# STM32F407.net
KiCad netlist of a schematic drawn in Altium Designer
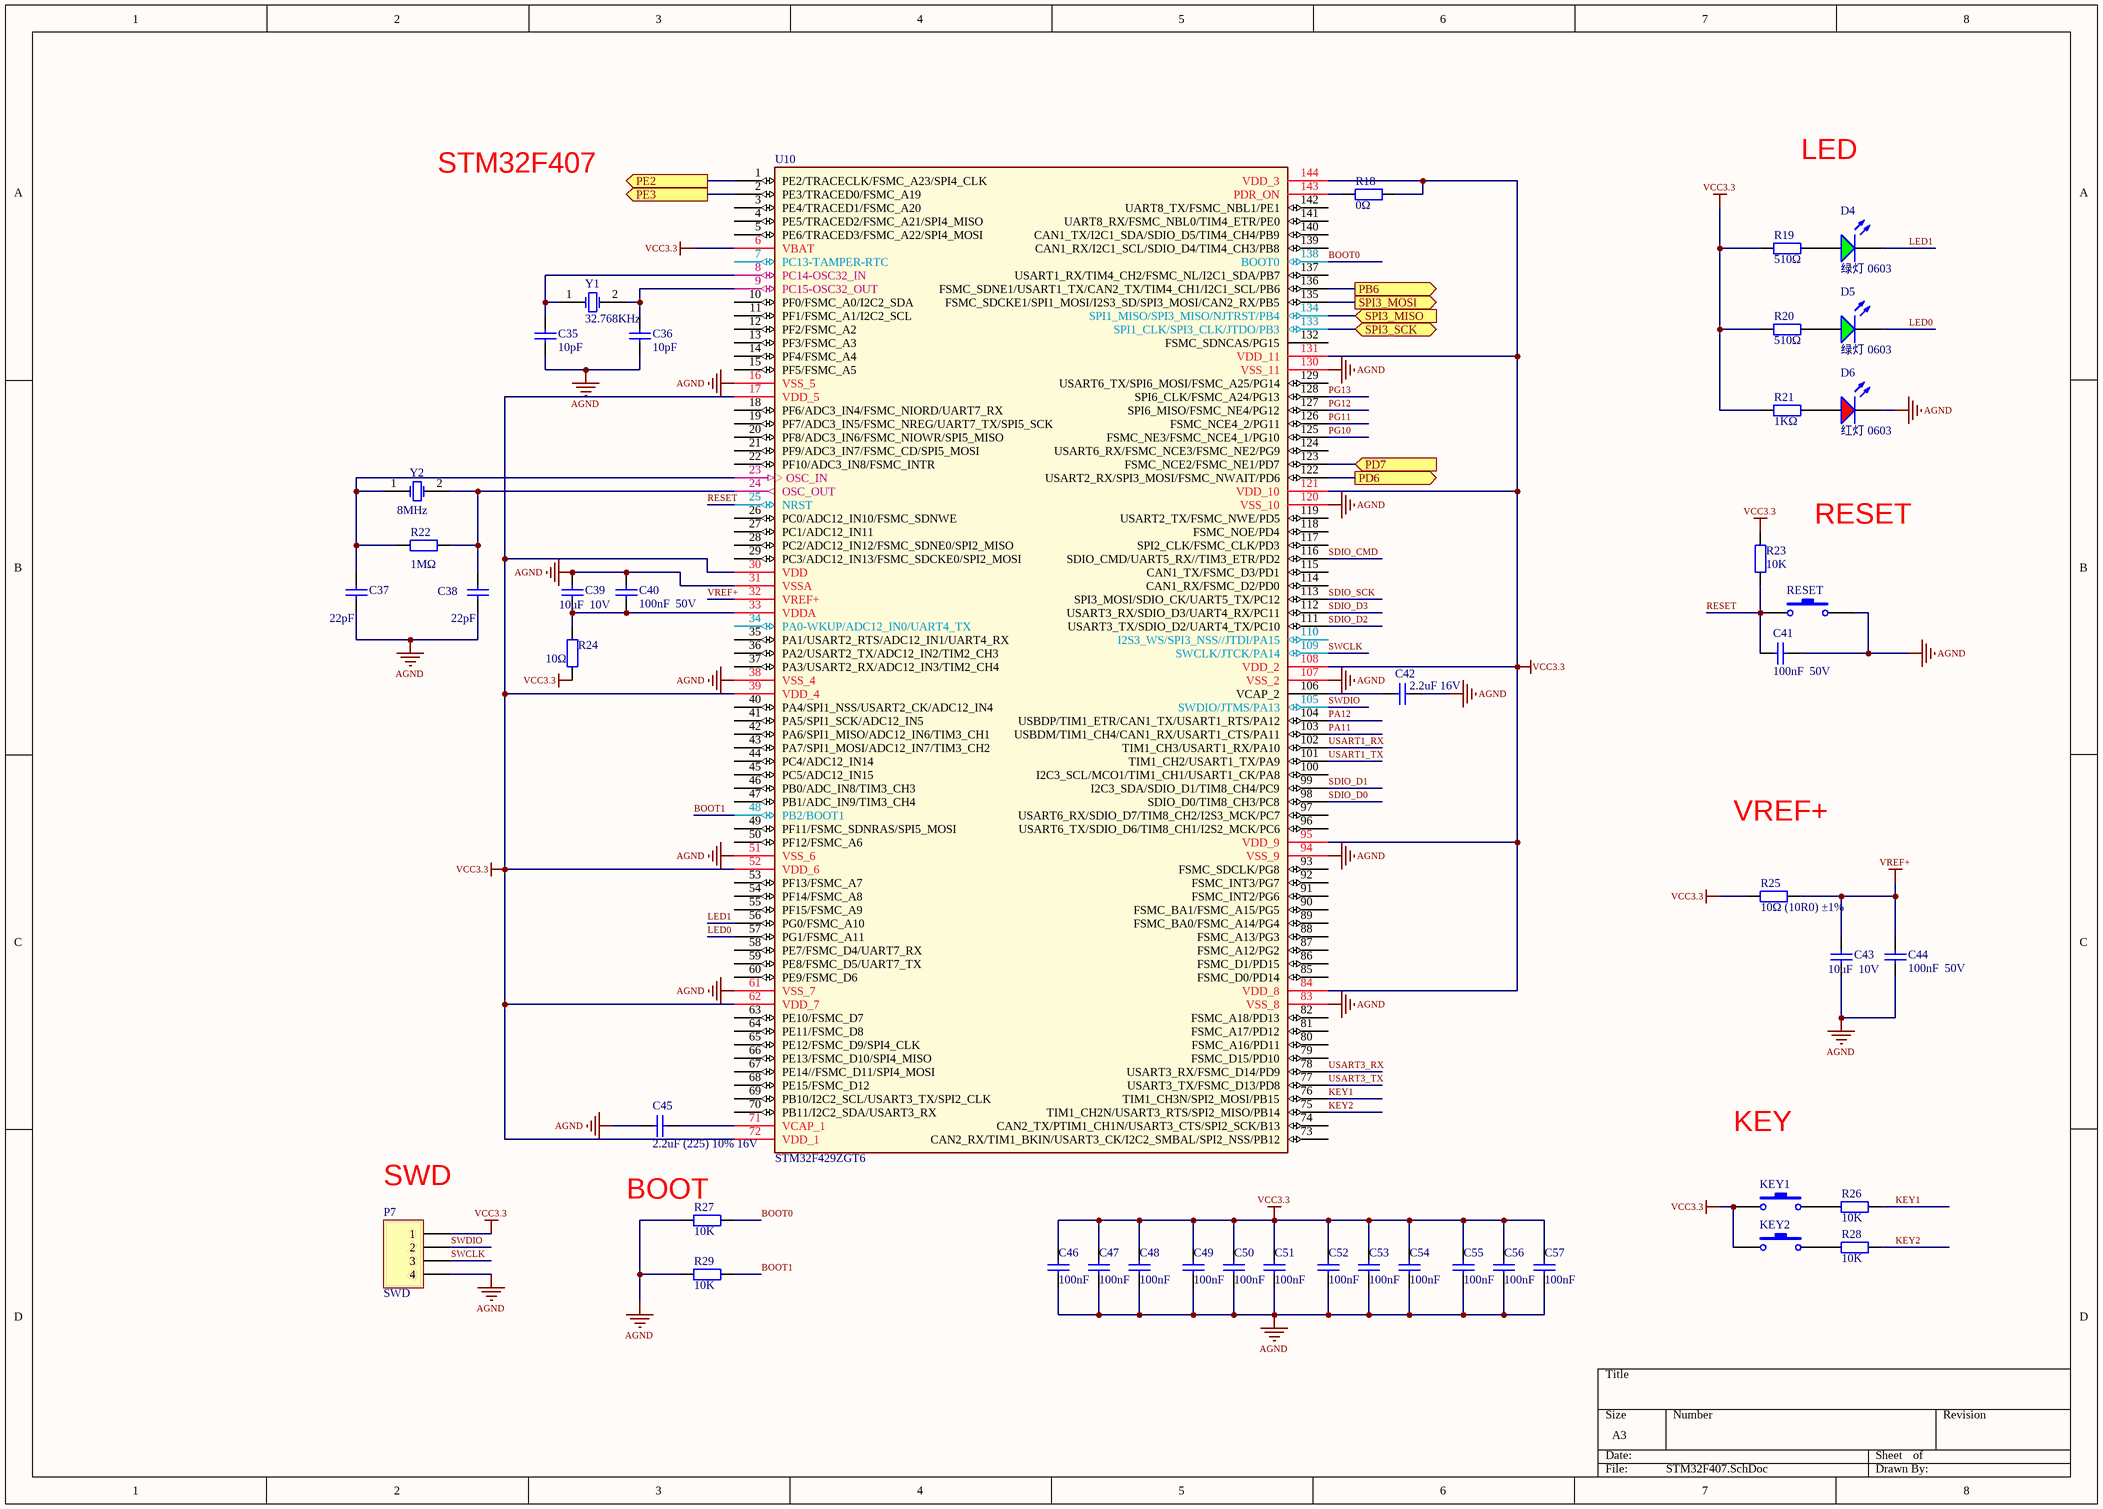
[diagram p0: STM32F407.SchDoc]

(export (version "E")
  (design (tool "Eeschema 10.0.6"))
  (components
    (comp (ref "C35")
      (value "10pF")
      (footprint "0402_C")
      (description "贴片电容")
      (libsource (lib "Miscellaneous Devices LC") (part "0603 10pF (100) 5% 50V"))
    )
    (comp (ref "C36")
      (value "10pF")
      (footprint "0402_C")
      (description "贴片电容")
      (libsource (lib "Miscellaneous Devices LC") (part "0603 10pF (100) 5% 50V"))
    )
    (comp (ref "C37")
      (value "22pF")
      (footprint "0402_C")
      (description "贴片电容")
      (libsource (lib "Miscellaneous Devices LC") (part "0603 22pF (220) 5% 50V"))
    )
    (comp (ref "C38")
      (value "22pF")
      (footprint "0402_C")
      (description "贴片电容")
      (libsource (lib "Miscellaneous Devices LC") (part "0603 22pF (220) 5% 50V"))
    )
    (comp (ref "C39")
      (value "10uF  10V")
      (footprint "0402_C")
      (description "贴片电容")
      (libsource (lib "Miscellaneous Devices LC") (part "0603 10uF (106) 10% 10V"))
    )
    (comp (ref "C40")
      (value "100nF  50V")
      (footprint "0402_C")
      (description "贴片电容")
      (libsource (lib "Miscellaneous Devices LC") (part "0603 100nF (104) 10% 50V"))
    )
    (comp (ref "C41")
      (value "100nF  50V")
      (footprint "0402_C")
      (description "贴片电容")
      (libsource (lib "Miscellaneous Devices LC") (part "0603 100nF (104) 10% 50V"))
    )
    (comp (ref "C42")
      (value "2.2uF 16V")
      (footprint "0603_C")
      (description "贴片电容")
      (libsource (lib "Miscellaneous Devices LC") (part "0603 2.2uF (225) 10% 16V"))
    )
    (comp (ref "C43")
      (value "10uF  10V")
      (footprint "0402_C")
      (description "贴片电容")
      (libsource (lib "Miscellaneous Devices LC") (part "0603 10uF (106) 10% 10V"))
    )
    (comp (ref "C44")
      (value "100nF  50V")
      (footprint "0402_C")
      (description "贴片电容")
      (libsource (lib "Miscellaneous Devices LC") (part "0603 100nF (104) 10% 50V"))
    )
    (comp (ref "C45")
      (value "2.2uF (225) 10% 16V")
      (footprint "0603_C")
      (description "贴片电容")
      (libsource (lib "Miscellaneous Devices LC") (part "0603 2.2uF (225) 10% 16V"))
    )
    (comp (ref "C46")
      (value "100nF")
      (footprint "0402_C")
      (description "贴片电容")
      (libsource (lib "Miscellaneous Devices LC") (part "0402 100nF (104) 10% 16V"))
    )
    (comp (ref "C47")
      (value "100nF")
      (footprint "0402_C")
      (description "贴片电容")
      (libsource (lib "Miscellaneous Devices LC") (part "0402 100nF (104) 10% 16V"))
    )
    (comp (ref "C48")
      (value "100nF")
      (footprint "0402_C")
      (description "贴片电容")
      (libsource (lib "Miscellaneous Devices LC") (part "0402 100nF (104) 10% 16V"))
    )
    (comp (ref "C49")
      (value "100nF")
      (footprint "0402_C")
      (description "贴片电容")
      (libsource (lib "Miscellaneous Devices LC") (part "0402 100nF (104) 10% 16V"))
    )
    (comp (ref "C50")
      (value "100nF")
      (footprint "0402_C")
      (description "贴片电容")
      (libsource (lib "Miscellaneous Devices LC") (part "0402 100nF (104) 10% 16V"))
    )
    (comp (ref "C51")
      (value "100nF")
      (footprint "0402_C")
      (description "贴片电容")
      (libsource (lib "Miscellaneous Devices LC") (part "0402 100nF (104) 10% 16V"))
    )
    (comp (ref "C52")
      (value "100nF")
      (footprint "0402_C")
      (description "贴片电容")
      (libsource (lib "Miscellaneous Devices LC") (part "0402 100nF (104) 10% 16V"))
    )
    (comp (ref "C53")
      (value "100nF")
      (footprint "0402_C")
      (description "贴片电容")
      (libsource (lib "Miscellaneous Devices LC") (part "0402 100nF (104) 10% 16V"))
    )
    (comp (ref "C54")
      (value "100nF")
      (footprint "0402_C")
      (description "贴片电容")
      (libsource (lib "Miscellaneous Devices LC") (part "0402 100nF (104) 10% 16V"))
    )
    (comp (ref "C55")
      (value "100nF")
      (footprint "0402_C")
      (description "贴片电容")
      (libsource (lib "Miscellaneous Devices LC") (part "0402 100nF (104) 10% 16V"))
    )
    (comp (ref "C56")
      (value "100nF")
      (footprint "0402_C")
      (description "贴片电容")
      (libsource (lib "Miscellaneous Devices LC") (part "0402 100nF (104) 10% 16V"))
    )
    (comp (ref "C57")
      (value "100nF")
      (footprint "0402_C")
      (description "贴片电容")
      (libsource (lib "Miscellaneous Devices LC") (part "0402 100nF (104) 10% 16V"))
    )
    (comp (ref "D4")
      (value "绿灯 0603")
      (footprint "0603_LED_S1")
      (description "发光二极管")
      (libsource (lib "Miscellaneous Devices LC") (part "0603 绿灯"))
    )
    (comp (ref "D5")
      (value "绿灯 0603")
      (footprint "0603_LED_S1")
      (description "发光二极管")
      (libsource (lib "Miscellaneous Devices LC") (part "0603 绿灯"))
    )
    (comp (ref "D6")
      (value "红灯 0603")
      (footprint "0603_LED_S1")
      (description "发光二极管")
      (libsource (lib "Miscellaneous Devices LC") (part "0603 红灯"))
    )
    (comp (ref "KEY1")
      (value "SW-PB")
      (footprint "KEY_3.6*2.5")
      (description "Switch")
      (fields (field (name "PUBLISHER") "Altium Limited"))
      (libsource (lib "Miscellaneous Devices") (part "SW-PB"))
    )
    (comp (ref "KEY2")
      (value "SW-PB")
      (footprint "KEY_3.6*2.5")
      (description "Switch")
      (fields (field (name "PUBLISHER") "Altium Limited"))
      (libsource (lib "Miscellaneous Devices") (part "SW-PB"))
    )
    (comp (ref "P7")
      (value "SWD")
      (footprint "HDR1X4")
      (description "Header, 4-Pin")
      (fields (field (name "PUBLISHER") "Altium Limited"))
      (libsource (lib "Miscellaneous Connectors") (part "Header 4"))
    )
    (comp (ref "R18")
      (value "0Ω")
      (footprint "0402_R")
      (description "贴片电阻")
      (libsource (lib "Miscellaneous Devices LC") (part "0603 0Ω (0R0) 1%"))
    )
    (comp (ref "R19")
      (value "510Ω")
      (footprint "0402_R")
      (description "贴片电阻")
      (libsource (lib "Miscellaneous Devices LC") (part "0603 510Ω (5100) 1%"))
    )
    (comp (ref "R20")
      (value "510Ω")
      (footprint "0402_R")
      (description "贴片电阻")
      (libsource (lib "Miscellaneous Devices LC") (part "0603 510Ω (5100) 1%"))
    )
    (comp (ref "R21")
      (value "1KΩ")
      (footprint "0402_R")
      (description "贴片电阻")
      (libsource (lib "Miscellaneous Devices LC") (part "0603 1KΩ (1001) 1%"))
    )
    (comp (ref "R22")
      (value "1MΩ")
      (footprint "0402_R")
      (description "贴片电阻")
      (libsource (lib "Miscellaneous Devices LC") (part "0603 1.2MΩ (1204) 1%"))
    )
    (comp (ref "R23")
      (value "10K")
      (footprint "0402_R")
      (description "贴片电阻")
      (libsource (lib "") (part "0603 10Ω (10R0) 1%_2"))
    )
    (comp (ref "R24")
      (value "10Ω")
      (footprint "0402_R")
      (description "贴片电阻")
      (libsource (lib "") (part "0603 10Ω (10R0) 1%_1"))
    )
    (comp (ref "R25")
      (value "10Ω (10R0) ±1%")
      (footprint "0402_R")
      (description "贴片电阻")
      (libsource (lib "") (part "0603 10Ω (10R0) 1%_3"))
    )
    (comp (ref "R26")
      (value "10K")
      (footprint "0402_R")
      (description "贴片电阻")
      (libsource (lib "Miscellaneous Devices LC") (part "0603 10Ω (10R0) 1%"))
    )
    (comp (ref "R27")
      (value "10K")
      (footprint "0402_R")
      (description "贴片电阻")
      (libsource (lib "Miscellaneous Devices LC") (part "0603 10Ω (10R0) 1%"))
    )
    (comp (ref "R28")
      (value "10K")
      (footprint "0402_R")
      (description "贴片电阻")
      (libsource (lib "Miscellaneous Devices LC") (part "0603 10Ω (10R0) 1%"))
    )
    (comp (ref "R29")
      (value "10K")
      (footprint "0402_R")
      (description "贴片电阻")
      (libsource (lib "Miscellaneous Devices LC") (part "0603 10Ω (10R0) 1%"))
    )
    (comp (ref "RESET")
      (value "SW-PB")
      (footprint "KEY_3.6*2.5")
      (description "Switch")
      (fields (field (name "PUBLISHER") "Altium Limited"))
      (libsource (lib "Miscellaneous Devices") (part "SW-PB"))
    )
    (comp (ref "U10")
      (value "STM32F429ZGT6")
      (footprint "LQFP-144_20x20x05P")
      (description "ARM")
      (libsource (lib "Miscellaneous Devices LC") (part "STM32F429ZGT6"))
    )
    (comp (ref "Y1")
      (value "32.768KHz")
      (footprint "SMD-3215_2P FC - 135")
      (description "贴片晶振")
      (libsource (lib "Miscellaneous Devices LC") (part "SMD-3215_2P 32.768KHz 20ppm 12.5pF"))
    )
    (comp (ref "Y2")
      (value "8MHz")
      (footprint "SMD-5032_2P")
      (description "贴片晶振")
      (libsource (lib "Miscellaneous Devices LC") (part "SMD-5032_2P 8MHz 20ppm 20pF"))
    )
  )
  (nets
    (net (code "1") (name "/BOOT0") (class "Default")
      (node (ref "R27") (pin "2") (pinfunction "2_2") (pintype "passive"))
      (node (ref "U10") (pin "138") (pinfunction "BOOT0_138") (pintype "bidirectional"))
    )
    (net (code "2") (name "/BOOT1") (class "Default")
      (node (ref "R29") (pin "2") (pinfunction "2_2") (pintype "passive"))
      (node (ref "U10") (pin "48") (pinfunction "PB2/BOOT1_48") (pintype "bidirectional"))
    )
    (net (code "3") (name "/KEY1") (class "Default")
      (node (ref "R26") (pin "2") (pinfunction "2_2") (pintype "passive"))
      (node (ref "U10") (pin "76") (pinfunction "TIM1_CH3N/SPI2_MOSI/PB15_76") (pintype "bidirectional"))
    )
    (net (code "4") (name "/KEY2") (class "Default")
      (node (ref "R28") (pin "2") (pinfunction "2_2") (pintype "passive"))
      (node (ref "U10") (pin "75") (pinfunction "TIM1_CH2N/USART3_RTS/SPI2_MISO/PB14_75") (pintype "bidirectional"))
    )
    (net (code "5") (name "/LED0") (class "Default")
      (node (ref "D5") (pin "K") (pinfunction "K_K") (pintype "passive"))
      (node (ref "U10") (pin "57") (pinfunction "PG1/FSMC_A11_57") (pintype "bidirectional"))
    )
    (net (code "6") (name "/LED1") (class "Default")
      (node (ref "D4") (pin "K") (pinfunction "K_K") (pintype "passive"))
      (node (ref "U10") (pin "56") (pinfunction "PG0/FSMC_A10_56") (pintype "bidirectional"))
    )
    (net (code "7") (name "/PA11") (class "Default")
      (node (ref "U10") (pin "103") (pinfunction "USBDM/TIM1_CH4/CAN1_RX/USART1_CTS/PA11_103") (pintype "bidirectional"))
    )
    (net (code "8") (name "/PA12") (class "Default")
      (node (ref "U10") (pin "104") (pinfunction "USBDP/TIM1_ETR/CAN1_TX/USART1_RTS/PA12_104") (pintype "bidirectional"))
    )
    (net (code "9") (name "/PB6") (class "Default")
      (node (ref "U10") (pin "136") (pinfunction "FSMC_SDNE1/USART1_TX/CAN2_TX/TIM4_CH1/I2C1_SCL/PB6_136") (pintype "bidirectional"))
    )
    (net (code "10") (name "/PD6") (class "Default")
      (node (ref "U10") (pin "122") (pinfunction "USART2_RX/SPI3_MOSI/FSMC_NWAIT/PD6_122") (pintype "bidirectional"))
    )
    (net (code "11") (name "/PD7") (class "Default")
      (node (ref "U10") (pin "123") (pinfunction "FSMC_NCE2/FSMC_NE1/PD7_123") (pintype "bidirectional"))
    )
    (net (code "12") (name "/PE2") (class "Default")
      (node (ref "U10") (pin "1") (pinfunction "PE2/TRACECLK/FSMC_A23/SPI4_CLK_1") (pintype "bidirectional"))
    )
    (net (code "13") (name "/PE3") (class "Default")
      (node (ref "U10") (pin "2") (pinfunction "PE3/TRACED0/FSMC_A19_2") (pintype "bidirectional"))
    )
    (net (code "14") (name "/PG10") (class "Default")
      (node (ref "U10") (pin "125") (pinfunction "FSMC_NE3/FSMC_NCE4_1/PG10_125") (pintype "bidirectional"))
    )
    (net (code "15") (name "/PG11") (class "Default")
      (node (ref "U10") (pin "126") (pinfunction "FSMC_NCE4_2/PG11_126") (pintype "bidirectional"))
    )
    (net (code "16") (name "/PG12") (class "Default")
      (node (ref "U10") (pin "127") (pinfunction "SPI6_MISO/FSMC_NE4/PG12_127") (pintype "bidirectional"))
    )
    (net (code "17") (name "/PG13") (class "Default")
      (node (ref "U10") (pin "128") (pinfunction "SPI6_CLK/FSMC_A24/PG13_128") (pintype "bidirectional"))
    )
    (net (code "18") (name "/RESET") (class "Default")
      (node (ref "C41") (pin "2") (pinfunction "2_2") (pintype "passive"))
      (node (ref "R23") (pin "2") (pinfunction "2_2") (pintype "passive"))
      (node (ref "RESET") (pin "1") (pinfunction "1_1") (pintype "passive"))
      (node (ref "U10") (pin "25") (pinfunction "NRST_25") (pintype "bidirectional"))
    )
    (net (code "19") (name "/SDIO_CMD") (class "Default")
      (node (ref "U10") (pin "116") (pinfunction "SDIO_CMD/UART5_RX//TIM3_ETR/PD2_116") (pintype "bidirectional"))
    )
    (net (code "20") (name "/SDIO_D0") (class "Default")
      (node (ref "U10") (pin "98") (pinfunction "SDIO_D0/TIM8_CH3/PC8_98") (pintype "bidirectional"))
    )
    (net (code "21") (name "/SDIO_D1") (class "Default")
      (node (ref "U10") (pin "99") (pinfunction "I2C3_SDA/SDIO_D1/TIM8_CH4/PC9_99") (pintype "bidirectional"))
    )
    (net (code "22") (name "/SDIO_D2") (class "Default")
      (node (ref "U10") (pin "111") (pinfunction "USART3_TX/SDIO_D2/UART4_TX/PC10_111") (pintype "bidirectional"))
    )
    (net (code "23") (name "/SDIO_D3") (class "Default")
      (node (ref "U10") (pin "112") (pinfunction "USART3_RX/SDIO_D3/UART4_RX/PC11_112") (pintype "bidirectional"))
    )
    (net (code "24") (name "/SDIO_SCK") (class "Default")
      (node (ref "U10") (pin "113") (pinfunction "SPI3_MOSI/SDIO_CK/UART5_TX/PC12_113") (pintype "bidirectional"))
    )
    (net (code "25") (name "/SPI3_MISO") (class "Default")
      (node (ref "U10") (pin "134") (pinfunction "SPI1_MISO/SPI3_MISO/NJTRST/PB4_134") (pintype "bidirectional"))
    )
    (net (code "26") (name "/SPI3_MOSI") (class "Default")
      (node (ref "U10") (pin "135") (pinfunction "FSMC_SDCKE1/SPI1_MOSI/I2S3_SD/SPI3_MOSI/CAN2_RX/PB5_135") (pintype "bidirectional"))
    )
    (net (code "27") (name "/SPI3_SCK") (class "Default")
      (node (ref "U10") (pin "133") (pinfunction "SPI1_CLK/SPI3_CLK/JTDO/PB3_133") (pintype "bidirectional"))
    )
    (net (code "28") (name "/SWCLK") (class "Default")
      (node (ref "P7") (pin "3") (pinfunction "3_3") (pintype "passive"))
      (node (ref "U10") (pin "109") (pinfunction "SWCLK/JTCK/PA14_109") (pintype "bidirectional"))
    )
    (net (code "29") (name "/SWDIO") (class "Default")
      (node (ref "P7") (pin "2") (pinfunction "2_2") (pintype "passive"))
      (node (ref "U10") (pin "105") (pinfunction "SWDIO/JTMS/PA13_105") (pintype "bidirectional"))
    )
    (net (code "30") (name "/USART1_RX") (class "Default")
      (node (ref "U10") (pin "102") (pinfunction "TIM1_CH3/USART1_RX/PA10_102") (pintype "bidirectional"))
    )
    (net (code "31") (name "/USART1_TX") (class "Default")
      (node (ref "U10") (pin "101") (pinfunction "TIM1_CH2/USART1_TX/PA9_101") (pintype "bidirectional"))
    )
    (net (code "32") (name "/USART3_RX") (class "Default")
      (node (ref "U10") (pin "78") (pinfunction "USART3_RX/FSMC_D14/PD9_78") (pintype "bidirectional"))
    )
    (net (code "33") (name "/USART3_TX") (class "Default")
      (node (ref "U10") (pin "77") (pinfunction "USART3_TX/FSMC_D13/PD8_77") (pintype "bidirectional"))
    )
    (net (code "34") (name "AGND") (class "Default")
      (node (ref "C35") (pin "1") (pinfunction "1_1") (pintype "passive"))
      (node (ref "C36") (pin "1") (pinfunction "1_1") (pintype "passive"))
      (node (ref "C37") (pin "1") (pinfunction "1_1") (pintype "passive"))
      (node (ref "C38") (pin "1") (pinfunction "1_1") (pintype "passive"))
      (node (ref "C39") (pin "2") (pinfunction "2_2") (pintype "passive"))
      (node (ref "C40") (pin "2") (pinfunction "2_2") (pintype "passive"))
      (node (ref "C41") (pin "1") (pinfunction "1_1") (pintype "passive"))
      (node (ref "C42") (pin "1") (pinfunction "1_1") (pintype "passive"))
      (node (ref "C43") (pin "1") (pinfunction "1_1") (pintype "passive"))
      (node (ref "C44") (pin "1") (pinfunction "1_1") (pintype "passive"))
      (node (ref "C45") (pin "1") (pinfunction "1_1") (pintype "passive"))
      (node (ref "C46") (pin "1") (pinfunction "1_1") (pintype "passive"))
      (node (ref "C47") (pin "1") (pinfunction "1_1") (pintype "passive"))
      (node (ref "C48") (pin "1") (pinfunction "1_1") (pintype "passive"))
      (node (ref "C49") (pin "1") (pinfunction "1_1") (pintype "passive"))
      (node (ref "C50") (pin "1") (pinfunction "1_1") (pintype "passive"))
      (node (ref "C51") (pin "1") (pinfunction "1_1") (pintype "passive"))
      (node (ref "C52") (pin "1") (pinfunction "1_1") (pintype "passive"))
      (node (ref "C53") (pin "1") (pinfunction "1_1") (pintype "passive"))
      (node (ref "C54") (pin "1") (pinfunction "1_1") (pintype "passive"))
      (node (ref "C55") (pin "1") (pinfunction "1_1") (pintype "passive"))
      (node (ref "C56") (pin "1") (pinfunction "1_1") (pintype "passive"))
      (node (ref "C57") (pin "1") (pinfunction "1_1") (pintype "passive"))
      (node (ref "D6") (pin "K") (pinfunction "K_K") (pintype "passive"))
      (node (ref "P7") (pin "4") (pinfunction "4_4") (pintype "passive"))
      (node (ref "R27") (pin "1") (pinfunction "1_1") (pintype "passive"))
      (node (ref "R29") (pin "1") (pinfunction "1_1") (pintype "passive"))
      (node (ref "RESET") (pin "2") (pinfunction "2_2") (pintype "passive"))
      (node (ref "U10") (pin "107") (pinfunction "VSS_2_107") (pintype "power_in"))
      (node (ref "U10") (pin "120") (pinfunction "VSS_10_120") (pintype "power_in"))
      (node (ref "U10") (pin "130") (pinfunction "VSS_11_130") (pintype "power_in"))
      (node (ref "U10") (pin "16") (pinfunction "VSS_5_16") (pintype "power_in"))
      (node (ref "U10") (pin "31") (pinfunction "VSSA_31") (pintype "power_in"))
      (node (ref "U10") (pin "38") (pinfunction "VSS_4_38") (pintype "power_in"))
      (node (ref "U10") (pin "51") (pinfunction "VSS_6_51") (pintype "power_in"))
      (node (ref "U10") (pin "61") (pinfunction "VSS_7_61") (pintype "power_in"))
      (node (ref "U10") (pin "83") (pinfunction "VSS_8_83") (pintype "power_in"))
      (node (ref "U10") (pin "94") (pinfunction "VSS_9_94") (pintype "power_in"))
    )
    (net (code "35") (name "Net-(D4-PadA)") (class "Default")
      (node (ref "D4") (pin "A") (pinfunction "A_A") (pintype "passive"))
      (node (ref "R19") (pin "2") (pinfunction "2_2") (pintype "passive"))
    )
    (net (code "36") (name "Net-(D5-PadA)") (class "Default")
      (node (ref "D5") (pin "A") (pinfunction "A_A") (pintype "passive"))
      (node (ref "R20") (pin "2") (pinfunction "2_2") (pintype "passive"))
    )
    (net (code "37") (name "Net-(D6-PadA)") (class "Default")
      (node (ref "D6") (pin "A") (pinfunction "A_A") (pintype "passive"))
      (node (ref "R21") (pin "2") (pinfunction "2_2") (pintype "passive"))
    )
    (net (code "38") (name "Net-(KEY1-Pad2)") (class "Default")
      (node (ref "KEY1") (pin "2") (pinfunction "2_2") (pintype "passive"))
      (node (ref "R26") (pin "1") (pinfunction "1_1") (pintype "passive"))
    )
    (net (code "39") (name "Net-(KEY2-Pad2)") (class "Default")
      (node (ref "KEY2") (pin "2") (pinfunction "2_2") (pintype "passive"))
      (node (ref "R28") (pin "1") (pinfunction "1_1") (pintype "passive"))
    )
    (net (code "40") (name "Net-(U10-OSC_IN)") (class "Default")
      (node (ref "C37") (pin "2") (pinfunction "2_2") (pintype "passive"))
      (node (ref "R22") (pin "1") (pinfunction "1_1") (pintype "passive"))
      (node (ref "U10") (pin "23") (pinfunction "OSC_IN_23") (pintype "input"))
      (node (ref "Y2") (pin "1") (pinfunction "OSC1_1") (pintype "passive"))
    )
    (net (code "41") (name "Net-(U10-OSC_OUT)") (class "Default")
      (node (ref "C38") (pin "2") (pinfunction "2_2") (pintype "passive"))
      (node (ref "R22") (pin "2") (pinfunction "2_2") (pintype "passive"))
      (node (ref "U10") (pin "24") (pinfunction "OSC_OUT_24") (pintype "output"))
      (node (ref "Y2") (pin "2") (pinfunction "OSC2_2") (pintype "passive"))
    )
    (net (code "42") (name "Net-(U10-PC14-OSC32_IN)") (class "Default")
      (node (ref "C35") (pin "2") (pinfunction "2_2") (pintype "passive"))
      (node (ref "U10") (pin "8") (pinfunction "PC14-OSC32_IN_8") (pintype "bidirectional"))
      (node (ref "Y1") (pin "1") (pinfunction "OSC1_1") (pintype "passive"))
    )
    (net (code "43") (name "Net-(U10-PC15-OSC32_OUT)") (class "Default")
      (node (ref "C36") (pin "2") (pinfunction "2_2") (pintype "passive"))
      (node (ref "U10") (pin "9") (pinfunction "PC15-OSC32_OUT_9") (pintype "bidirectional"))
      (node (ref "Y1") (pin "2") (pinfunction "OSC2_2") (pintype "passive"))
    )
    (net (code "44") (name "Net-(U10-PDR_ON)") (class "Default")
      (node (ref "R18") (pin "2") (pinfunction "2_2") (pintype "passive"))
      (node (ref "U10") (pin "143") (pinfunction "PDR_ON_143") (pintype "power_in"))
    )
    (net (code "45") (name "Net-(U10-VCAP_1)") (class "Default")
      (node (ref "C45") (pin "2") (pinfunction "2_2") (pintype "passive"))
      (node (ref "U10") (pin "71") (pinfunction "VCAP_1_71") (pintype "power_in"))
    )
    (net (code "46") (name "Net-(U10-VCAP_2)") (class "Default")
      (node (ref "C42") (pin "2") (pinfunction "2_2") (pintype "passive"))
      (node (ref "U10") (pin "106") (pinfunction "VCAP_2_106") (pintype "tri_state"))
    )
    (net (code "47") (name "Net-(U10-VDDA)") (class "Default")
      (node (ref "C39") (pin "1") (pinfunction "1_1") (pintype "passive"))
      (node (ref "C40") (pin "1") (pinfunction "1_1") (pintype "passive"))
      (node (ref "R24") (pin "2") (pinfunction "2_2") (pintype "passive"))
      (node (ref "U10") (pin "33") (pinfunction "VDDA_33") (pintype "power_in"))
    )
    (net (code "48") (name "VCC3.3") (class "Default")
      (node (ref "C46") (pin "2") (pinfunction "2_2") (pintype "passive"))
      (node (ref "C47") (pin "2") (pinfunction "2_2") (pintype "passive"))
      (node (ref "C48") (pin "2") (pinfunction "2_2") (pintype "passive"))
      (node (ref "C49") (pin "2") (pinfunction "2_2") (pintype "passive"))
      (node (ref "C50") (pin "2") (pinfunction "2_2") (pintype "passive"))
      (node (ref "C51") (pin "2") (pinfunction "2_2") (pintype "passive"))
      (node (ref "C52") (pin "2") (pinfunction "2_2") (pintype "passive"))
      (node (ref "C53") (pin "2") (pinfunction "2_2") (pintype "passive"))
      (node (ref "C54") (pin "2") (pinfunction "2_2") (pintype "passive"))
      (node (ref "C55") (pin "2") (pinfunction "2_2") (pintype "passive"))
      (node (ref "C56") (pin "2") (pinfunction "2_2") (pintype "passive"))
      (node (ref "C57") (pin "2") (pinfunction "2_2") (pintype "passive"))
      (node (ref "KEY1") (pin "1") (pinfunction "1_1") (pintype "passive"))
      (node (ref "KEY2") (pin "1") (pinfunction "1_1") (pintype "passive"))
      (node (ref "P7") (pin "1") (pinfunction "1_1") (pintype "passive"))
      (node (ref "R18") (pin "1") (pinfunction "1_1") (pintype "passive"))
      (node (ref "R19") (pin "1") (pinfunction "1_1") (pintype "passive"))
      (node (ref "R20") (pin "1") (pinfunction "1_1") (pintype "passive"))
      (node (ref "R21") (pin "1") (pinfunction "1_1") (pintype "passive"))
      (node (ref "R23") (pin "1") (pinfunction "1_1") (pintype "passive"))
      (node (ref "R24") (pin "1") (pinfunction "1_1") (pintype "passive"))
      (node (ref "R25") (pin "2") (pinfunction "2_2") (pintype "passive"))
      (node (ref "U10") (pin "108") (pinfunction "VDD_2_108") (pintype "power_in"))
      (node (ref "U10") (pin "121") (pinfunction "VDD_10_121") (pintype "power_in"))
      (node (ref "U10") (pin "131") (pinfunction "VDD_11_131") (pintype "power_in"))
      (node (ref "U10") (pin "144") (pinfunction "VDD_3_144") (pintype "power_in"))
      (node (ref "U10") (pin "17") (pinfunction "VDD_5_17") (pintype "power_in"))
      (node (ref "U10") (pin "30") (pinfunction "VDD_30") (pintype "power_in"))
      (node (ref "U10") (pin "39") (pinfunction "VDD_4_39") (pintype "power_in"))
      (node (ref "U10") (pin "52") (pinfunction "VDD_6_52") (pintype "power_in"))
      (node (ref "U10") (pin "6") (pinfunction "VBAT_6") (pintype "power_in"))
      (node (ref "U10") (pin "62") (pinfunction "VDD_7_62") (pintype "power_in"))
      (node (ref "U10") (pin "72") (pinfunction "VDD_1_72") (pintype "power_in"))
      (node (ref "U10") (pin "84") (pinfunction "VDD_8_84") (pintype "power_in"))
      (node (ref "U10") (pin "95") (pinfunction "VDD_9_95") (pintype "power_in"))
    )
    (net (code "49") (name "VREF+") (class "Default")
      (node (ref "C43") (pin "2") (pinfunction "2_2") (pintype "passive"))
      (node (ref "C44") (pin "2") (pinfunction "2_2") (pintype "passive"))
      (node (ref "R25") (pin "1") (pinfunction "1_1") (pintype "passive"))
      (node (ref "U10") (pin "32") (pinfunction "VREF+_32") (pintype "power_in"))
    )
    (net (code "50") (name "unconnected-(U10-CAN1_RX{slash}FSMC_D2{slash}PD0-Pad114)") (class "Default")
      (node (ref "U10") (pin "114") (pinfunction "CAN1_RX/FSMC_D2/PD0_114") (pintype "bidirectional"))
    )
    (net (code "51") (name "unconnected-(U10-CAN1_RX{slash}I2C1_SCL{slash}SDIO_D4{slash}TIM4_CH3{slash}PB8-Pad139)") (class "Default")
      (node (ref "U10") (pin "139") (pinfunction "CAN1_RX/I2C1_SCL/SDIO_D4/TIM4_CH3/PB8_139") (pintype "bidirectional"))
    )
    (net (code "52") (name "unconnected-(U10-CAN1_TX{slash}FSMC_D3{slash}PD1-Pad115)") (class "Default")
      (node (ref "U10") (pin "115") (pinfunction "CAN1_TX/FSMC_D3/PD1_115") (pintype "bidirectional"))
    )
    (net (code "53") (name "unconnected-(U10-CAN1_TX{slash}I2C1_SDA{slash}SDIO_D5{slash}TIM4_CH4{slash}PB9-Pad140)") (class "Default")
      (node (ref "U10") (pin "140") (pinfunction "CAN1_TX/I2C1_SDA/SDIO_D5/TIM4_CH4/PB9_140") (pintype "bidirectional"))
    )
    (net (code "54") (name "unconnected-(U10-CAN2_RX{slash}TIM1_BKIN{slash}USART3_CK{slash}I2C2_SMBAL{slash}SPI2_NSS{slash}PB12-Pad73)") (class "Default")
      (node (ref "U10") (pin "73") (pinfunction "CAN2_RX/TIM1_BKIN/USART3_CK/I2C2_SMBAL/SPI2_NSS/PB12_73") (pintype "bidirectional"))
    )
    (net (code "55") (name "unconnected-(U10-CAN2_TX{slash}PTIM1_CH1N{slash}USART3_CTS{slash}SPI2_SCK{slash}B13-Pad74)") (class "Default")
      (node (ref "U10") (pin "74") (pinfunction "CAN2_TX/PTIM1_CH1N/USART3_CTS/SPI2_SCK/B13_74") (pintype "bidirectional"))
    )
    (net (code "56") (name "unconnected-(U10-FSMC_A12{slash}PG2-Pad87)") (class "Default")
      (node (ref "U10") (pin "87") (pinfunction "FSMC_A12/PG2_87") (pintype "bidirectional"))
    )
    (net (code "57") (name "unconnected-(U10-FSMC_A13{slash}PG3-Pad88)") (class "Default")
      (node (ref "U10") (pin "88") (pinfunction "FSMC_A13/PG3_88") (pintype "bidirectional"))
    )
    (net (code "58") (name "unconnected-(U10-FSMC_A16{slash}PD11-Pad80)") (class "Default")
      (node (ref "U10") (pin "80") (pinfunction "FSMC_A16/PD11_80") (pintype "bidirectional"))
    )
    (net (code "59") (name "unconnected-(U10-FSMC_A17{slash}PD12-Pad81)") (class "Default")
      (node (ref "U10") (pin "81") (pinfunction "FSMC_A17/PD12_81") (pintype "bidirectional"))
    )
    (net (code "60") (name "unconnected-(U10-FSMC_A18{slash}PD13-Pad82)") (class "Default")
      (node (ref "U10") (pin "82") (pinfunction "FSMC_A18/PD13_82") (pintype "bidirectional"))
    )
    (net (code "61") (name "unconnected-(U10-FSMC_BA0{slash}FSMC_A14{slash}PG4-Pad89)") (class "Default")
      (node (ref "U10") (pin "89") (pinfunction "FSMC_BA0/FSMC_A14/PG4_89") (pintype "bidirectional"))
    )
    (net (code "62") (name "unconnected-(U10-FSMC_BA1{slash}FSMC_A15{slash}PG5-Pad90)") (class "Default")
      (node (ref "U10") (pin "90") (pinfunction "FSMC_BA1/FSMC_A15/PG5_90") (pintype "bidirectional"))
    )
    (net (code "63") (name "unconnected-(U10-FSMC_D0{slash}PD14-Pad85)") (class "Default")
      (node (ref "U10") (pin "85") (pinfunction "FSMC_D0/PD14_85") (pintype "bidirectional"))
    )
    (net (code "64") (name "unconnected-(U10-FSMC_D1{slash}PD15-Pad86)") (class "Default")
      (node (ref "U10") (pin "86") (pinfunction "FSMC_D1/PD15_86") (pintype "bidirectional"))
    )
    (net (code "65") (name "unconnected-(U10-FSMC_D15{slash}PD10-Pad79)") (class "Default")
      (node (ref "U10") (pin "79") (pinfunction "FSMC_D15/PD10_79") (pintype "bidirectional"))
    )
    (net (code "66") (name "unconnected-(U10-FSMC_INT2{slash}PG6-Pad91)") (class "Default")
      (node (ref "U10") (pin "91") (pinfunction "FSMC_INT2/PG6_91") (pintype "bidirectional"))
    )
    (net (code "67") (name "unconnected-(U10-FSMC_INT3{slash}PG7-Pad92)") (class "Default")
      (node (ref "U10") (pin "92") (pinfunction "FSMC_INT3/PG7_92") (pintype "bidirectional"))
    )
    (net (code "68") (name "unconnected-(U10-FSMC_NOE{slash}PD4-Pad118)") (class "Default")
      (node (ref "U10") (pin "118") (pinfunction "FSMC_NOE/PD4_118") (pintype "bidirectional"))
    )
    (net (code "69") (name "unconnected-(U10-FSMC_SDCLK{slash}PG8-Pad93)") (class "Default")
      (node (ref "U10") (pin "93") (pinfunction "FSMC_SDCLK/PG8_93") (pintype "bidirectional"))
    )
    (net (code "70") (name "unconnected-(U10-FSMC_SDNCAS{slash}PG15-Pad132)") (class "Default")
      (node (ref "U10") (pin "132") (pinfunction "FSMC_SDNCAS/PG15_132") (pintype "passive"))
    )
    (net (code "71") (name "unconnected-(U10-I2C3_SCL{slash}MCO1{slash}TIM1_CH1{slash}USART1_CK{slash}PA8-Pad100)") (class "Default")
      (node (ref "U10") (pin "100") (pinfunction "I2C3_SCL/MCO1/TIM1_CH1/USART1_CK/PA8_100") (pintype "bidirectional"))
    )
    (net (code "72") (name "unconnected-(U10-I2S3_WS{slash}SPI3_NSS{slash}{slash}JTDI{slash}PA15-Pad110)") (class "Default")
      (node (ref "U10") (pin "110") (pinfunction "I2S3_WS/SPI3_NSS//JTDI/PA15_110") (pintype "bidirectional"))
    )
    (net (code "73") (name "unconnected-(U10-PA0-WKUP{slash}ADC12_IN0{slash}UART4_TX-Pad34)") (class "Default")
      (node (ref "U10") (pin "34") (pinfunction "PA0-WKUP/ADC12_IN0/UART4_TX_34") (pintype "bidirectional"))
    )
    (net (code "74") (name "unconnected-(U10-PA1{slash}USART2_RTS{slash}ADC12_IN1{slash}UART4_RX-Pad35)") (class "Default")
      (node (ref "U10") (pin "35") (pinfunction "PA1/USART2_RTS/ADC12_IN1/UART4_RX_35") (pintype "bidirectional"))
    )
    (net (code "75") (name "unconnected-(U10-PA2{slash}USART2_TX{slash}ADC12_IN2{slash}TIM2_CH3-Pad36)") (class "Default")
      (node (ref "U10") (pin "36") (pinfunction "PA2/USART2_TX/ADC12_IN2/TIM2_CH3_36") (pintype "bidirectional"))
    )
    (net (code "76") (name "unconnected-(U10-PA3{slash}USART2_RX{slash}ADC12_IN3{slash}TIM2_CH4-Pad37)") (class "Default")
      (node (ref "U10") (pin "37") (pinfunction "PA3/USART2_RX/ADC12_IN3/TIM2_CH4_37") (pintype "bidirectional"))
    )
    (net (code "77") (name "unconnected-(U10-PA4{slash}SPI1_NSS{slash}USART2_CK{slash}ADC12_IN4-Pad40)") (class "Default")
      (node (ref "U10") (pin "40") (pinfunction "PA4/SPI1_NSS/USART2_CK/ADC12_IN4_40") (pintype "bidirectional"))
    )
    (net (code "78") (name "unconnected-(U10-PA5{slash}SPI1_SCK{slash}ADC12_IN5-Pad41)") (class "Default")
      (node (ref "U10") (pin "41") (pinfunction "PA5/SPI1_SCK/ADC12_IN5_41") (pintype "bidirectional"))
    )
    (net (code "79") (name "unconnected-(U10-PA6{slash}SPI1_MISO{slash}ADC12_IN6{slash}TIM3_CH1-Pad42)") (class "Default")
      (node (ref "U10") (pin "42") (pinfunction "PA6/SPI1_MISO/ADC12_IN6/TIM3_CH1_42") (pintype "bidirectional"))
    )
    (net (code "80") (name "unconnected-(U10-PA7{slash}SPI1_MOSI{slash}ADC12_IN7{slash}TIM3_CH2-Pad43)") (class "Default")
      (node (ref "U10") (pin "43") (pinfunction "PA7/SPI1_MOSI/ADC12_IN7/TIM3_CH2_43") (pintype "bidirectional"))
    )
    (net (code "81") (name "unconnected-(U10-PB0{slash}ADC_IN8{slash}TIM3_CH3-Pad46)") (class "Default")
      (node (ref "U10") (pin "46") (pinfunction "PB0/ADC_IN8/TIM3_CH3_46") (pintype "bidirectional"))
    )
    (net (code "82") (name "unconnected-(U10-PB1{slash}ADC_IN9{slash}TIM3_CH4-Pad47)") (class "Default")
      (node (ref "U10") (pin "47") (pinfunction "PB1/ADC_IN9/TIM3_CH4_47") (pintype "bidirectional"))
    )
    (net (code "83") (name "unconnected-(U10-PB10{slash}I2C2_SCL{slash}USART3_TX{slash}SPI2_CLK-Pad69)") (class "Default")
      (node (ref "U10") (pin "69") (pinfunction "PB10/I2C2_SCL/USART3_TX/SPI2_CLK_69") (pintype "bidirectional"))
    )
    (net (code "84") (name "unconnected-(U10-PB11{slash}I2C2_SDA{slash}USART3_RX-Pad70)") (class "Default")
      (node (ref "U10") (pin "70") (pinfunction "PB11/I2C2_SDA/USART3_RX_70") (pintype "bidirectional"))
    )
    (net (code "85") (name "unconnected-(U10-PC0{slash}ADC12_IN10{slash}FSMC_SDNWE-Pad26)") (class "Default")
      (node (ref "U10") (pin "26") (pinfunction "PC0/ADC12_IN10/FSMC_SDNWE_26") (pintype "bidirectional"))
    )
    (net (code "86") (name "unconnected-(U10-PC1{slash}ADC12_IN11-Pad27)") (class "Default")
      (node (ref "U10") (pin "27") (pinfunction "PC1/ADC12_IN11_27") (pintype "bidirectional"))
    )
    (net (code "87") (name "unconnected-(U10-PC2{slash}ADC12_IN12{slash}FSMC_SDNE0{slash}SPI2_MISO-Pad28)") (class "Default")
      (node (ref "U10") (pin "28") (pinfunction "PC2/ADC12_IN12/FSMC_SDNE0/SPI2_MISO_28") (pintype "bidirectional"))
    )
    (net (code "88") (name "unconnected-(U10-PC3{slash}ADC12_IN13{slash}FSMC_SDCKE0{slash}SPI2_MOSI-Pad29)") (class "Default")
      (node (ref "U10") (pin "29") (pinfunction "PC3/ADC12_IN13/FSMC_SDCKE0/SPI2_MOSI_29") (pintype "bidirectional"))
    )
    (net (code "89") (name "unconnected-(U10-PC4{slash}ADC12_IN14-Pad44)") (class "Default")
      (node (ref "U10") (pin "44") (pinfunction "PC4/ADC12_IN14_44") (pintype "bidirectional"))
    )
    (net (code "90") (name "unconnected-(U10-PC5{slash}ADC12_IN15-Pad45)") (class "Default")
      (node (ref "U10") (pin "45") (pinfunction "PC5/ADC12_IN15_45") (pintype "bidirectional"))
    )
    (net (code "91") (name "unconnected-(U10-PC13-TAMPER-RTC-Pad7)") (class "Default")
      (node (ref "U10") (pin "7") (pinfunction "PC13-TAMPER-RTC_7") (pintype "bidirectional"))
    )
    (net (code "92") (name "unconnected-(U10-PE4{slash}TRACED1{slash}FSMC_A20-Pad3)") (class "Default")
      (node (ref "U10") (pin "3") (pinfunction "PE4/TRACED1/FSMC_A20_3") (pintype "bidirectional"))
    )
    (net (code "93") (name "unconnected-(U10-PE5{slash}TRACED2{slash}FSMC_A21{slash}SPI4_MISO-Pad4)") (class "Default")
      (node (ref "U10") (pin "4") (pinfunction "PE5/TRACED2/FSMC_A21/SPI4_MISO_4") (pintype "bidirectional"))
    )
    (net (code "94") (name "unconnected-(U10-PE6{slash}TRACED3{slash}FSMC_A22{slash}SPI4_MOSI-Pad5)") (class "Default")
      (node (ref "U10") (pin "5") (pinfunction "PE6/TRACED3/FSMC_A22/SPI4_MOSI_5") (pintype "bidirectional"))
    )
    (net (code "95") (name "unconnected-(U10-PE7{slash}FSMC_D4{slash}UART7_RX-Pad58)") (class "Default")
      (node (ref "U10") (pin "58") (pinfunction "PE7/FSMC_D4/UART7_RX_58") (pintype "bidirectional"))
    )
    (net (code "96") (name "unconnected-(U10-PE8{slash}FSMC_D5{slash}UART7_TX-Pad59)") (class "Default")
      (node (ref "U10") (pin "59") (pinfunction "PE8/FSMC_D5/UART7_TX_59") (pintype "bidirectional"))
    )
    (net (code "97") (name "unconnected-(U10-PE9{slash}FSMC_D6-Pad60)") (class "Default")
      (node (ref "U10") (pin "60") (pinfunction "PE9/FSMC_D6_60") (pintype "bidirectional"))
    )
    (net (code "98") (name "unconnected-(U10-PE10{slash}FSMC_D7-Pad63)") (class "Default")
      (node (ref "U10") (pin "63") (pinfunction "PE10/FSMC_D7_63") (pintype "bidirectional"))
    )
    (net (code "99") (name "unconnected-(U10-PE11{slash}FSMC_D8-Pad64)") (class "Default")
      (node (ref "U10") (pin "64") (pinfunction "PE11/FSMC_D8_64") (pintype "bidirectional"))
    )
    (net (code "100") (name "unconnected-(U10-PE12{slash}FSMC_D9{slash}SPI4_CLK-Pad65)") (class "Default")
      (node (ref "U10") (pin "65") (pinfunction "PE12/FSMC_D9/SPI4_CLK_65") (pintype "bidirectional"))
    )
    (net (code "101") (name "unconnected-(U10-PE13{slash}FSMC_D10{slash}SPI4_MISO-Pad66)") (class "Default")
      (node (ref "U10") (pin "66") (pinfunction "PE13/FSMC_D10/SPI4_MISO_66") (pintype "bidirectional"))
    )
    (net (code "102") (name "unconnected-(U10-PE14{slash}{slash}FSMC_D11{slash}SPI4_MOSI-Pad67)") (class "Default")
      (node (ref "U10") (pin "67") (pinfunction "PE14//FSMC_D11/SPI4_MOSI_67") (pintype "bidirectional"))
    )
    (net (code "103") (name "unconnected-(U10-PE15{slash}FSMC_D12-Pad68)") (class "Default")
      (node (ref "U10") (pin "68") (pinfunction "PE15/FSMC_D12_68") (pintype "bidirectional"))
    )
    (net (code "104") (name "unconnected-(U10-PF0{slash}FSMC_A0{slash}I2C2_SDA-Pad10)") (class "Default")
      (node (ref "U10") (pin "10") (pinfunction "PF0/FSMC_A0/I2C2_SDA_10") (pintype "bidirectional"))
    )
    (net (code "105") (name "unconnected-(U10-PF1{slash}FSMC_A1{slash}I2C2_SCL-Pad11)") (class "Default")
      (node (ref "U10") (pin "11") (pinfunction "PF1/FSMC_A1/I2C2_SCL_11") (pintype "bidirectional"))
    )
    (net (code "106") (name "unconnected-(U10-PF2{slash}FSMC_A2-Pad12)") (class "Default")
      (node (ref "U10") (pin "12") (pinfunction "PF2/FSMC_A2_12") (pintype "bidirectional"))
    )
    (net (code "107") (name "unconnected-(U10-PF3{slash}FSMC_A3-Pad13)") (class "Default")
      (node (ref "U10") (pin "13") (pinfunction "PF3/FSMC_A3_13") (pintype "bidirectional"))
    )
    (net (code "108") (name "unconnected-(U10-PF4{slash}FSMC_A4-Pad14)") (class "Default")
      (node (ref "U10") (pin "14") (pinfunction "PF4/FSMC_A4_14") (pintype "bidirectional"))
    )
    (net (code "109") (name "unconnected-(U10-PF5{slash}FSMC_A5-Pad15)") (class "Default")
      (node (ref "U10") (pin "15") (pinfunction "PF5/FSMC_A5_15") (pintype "bidirectional"))
    )
    (net (code "110") (name "unconnected-(U10-PF6{slash}ADC3_IN4{slash}FSMC_NIORD{slash}UART7_RX-Pad18)") (class "Default")
      (node (ref "U10") (pin "18") (pinfunction "PF6/ADC3_IN4/FSMC_NIORD/UART7_RX_18") (pintype "bidirectional"))
    )
    (net (code "111") (name "unconnected-(U10-PF7{slash}ADC3_IN5{slash}FSMC_NREG{slash}UART7_TX{slash}SPI5_SCK-Pad19)") (class "Default")
      (node (ref "U10") (pin "19") (pinfunction "PF7/ADC3_IN5/FSMC_NREG/UART7_TX/SPI5_SCK_19") (pintype "bidirectional"))
    )
    (net (code "112") (name "unconnected-(U10-PF8{slash}ADC3_IN6{slash}FSMC_NIOWR{slash}SPI5_MISO-Pad20)") (class "Default")
      (node (ref "U10") (pin "20") (pinfunction "PF8/ADC3_IN6/FSMC_NIOWR/SPI5_MISO_20") (pintype "bidirectional"))
    )
    (net (code "113") (name "unconnected-(U10-PF9{slash}ADC3_IN7{slash}FSMC_CD{slash}SPI5_MOSI-Pad21)") (class "Default")
      (node (ref "U10") (pin "21") (pinfunction "PF9/ADC3_IN7/FSMC_CD/SPI5_MOSI_21") (pintype "bidirectional"))
    )
    (net (code "114") (name "unconnected-(U10-PF10{slash}ADC3_IN8{slash}FSMC_INTR-Pad22)") (class "Default")
      (node (ref "U10") (pin "22") (pinfunction "PF10/ADC3_IN8/FSMC_INTR_22") (pintype "bidirectional"))
    )
    (net (code "115") (name "unconnected-(U10-PF11{slash}FSMC_SDNRAS{slash}SPI5_MOSI-Pad49)") (class "Default")
      (node (ref "U10") (pin "49") (pinfunction "PF11/FSMC_SDNRAS/SPI5_MOSI_49") (pintype "bidirectional"))
    )
    (net (code "116") (name "unconnected-(U10-PF12{slash}FSMC_A6-Pad50)") (class "Default")
      (node (ref "U10") (pin "50") (pinfunction "PF12/FSMC_A6_50") (pintype "bidirectional"))
    )
    (net (code "117") (name "unconnected-(U10-PF13{slash}FSMC_A7-Pad53)") (class "Default")
      (node (ref "U10") (pin "53") (pinfunction "PF13/FSMC_A7_53") (pintype "bidirectional"))
    )
    (net (code "118") (name "unconnected-(U10-PF14{slash}FSMC_A8-Pad54)") (class "Default")
      (node (ref "U10") (pin "54") (pinfunction "PF14/FSMC_A8_54") (pintype "bidirectional"))
    )
    (net (code "119") (name "unconnected-(U10-PF15{slash}FSMC_A9-Pad55)") (class "Default")
      (node (ref "U10") (pin "55") (pinfunction "PF15/FSMC_A9_55") (pintype "bidirectional"))
    )
    (net (code "120") (name "unconnected-(U10-SPI2_CLK{slash}FSMC_CLK{slash}PD3-Pad117)") (class "Default")
      (node (ref "U10") (pin "117") (pinfunction "SPI2_CLK/FSMC_CLK/PD3_117") (pintype "bidirectional"))
    )
    (net (code "121") (name "unconnected-(U10-UART8_RX{slash}FSMC_NBL0{slash}TIM4_ETR{slash}PE0-Pad141)") (class "Default")
      (node (ref "U10") (pin "141") (pinfunction "UART8_RX/FSMC_NBL0/TIM4_ETR/PE0_141") (pintype "bidirectional"))
    )
    (net (code "122") (name "unconnected-(U10-UART8_TX{slash}FSMC_NBL1{slash}PE1-Pad142)") (class "Default")
      (node (ref "U10") (pin "142") (pinfunction "UART8_TX/FSMC_NBL1/PE1_142") (pintype "bidirectional"))
    )
    (net (code "123") (name "unconnected-(U10-USART1_RX{slash}TIM4_CH2{slash}FSMC_NL{slash}I2C1_SDA{slash}PB7-Pad137)") (class "Default")
      (node (ref "U10") (pin "137") (pinfunction "USART1_RX/TIM4_CH2/FSMC_NL/I2C1_SDA/PB7_137") (pintype "bidirectional"))
    )
    (net (code "124") (name "unconnected-(U10-USART2_TX{slash}FSMC_NWE{slash}PD5-Pad119)") (class "Default")
      (node (ref "U10") (pin "119") (pinfunction "USART2_TX/FSMC_NWE/PD5_119") (pintype "bidirectional"))
    )
    (net (code "125") (name "unconnected-(U10-USART6_RX{slash}FSMC_NCE3{slash}FSMC_NE2{slash}PG9-Pad124)") (class "Default")
      (node (ref "U10") (pin "124") (pinfunction "USART6_RX/FSMC_NCE3/FSMC_NE2/PG9_124") (pintype "bidirectional"))
    )
    (net (code "126") (name "unconnected-(U10-USART6_RX{slash}SDIO_D7{slash}TIM8_CH2{slash}I2S3_MCK{slash}PC7-Pad97)") (class "Default")
      (node (ref "U10") (pin "97") (pinfunction "USART6_RX/SDIO_D7/TIM8_CH2/I2S3_MCK/PC7_97") (pintype "bidirectional"))
    )
    (net (code "127") (name "unconnected-(U10-USART6_TX{slash}SDIO_D6{slash}TIM8_CH1{slash}I2S2_MCK{slash}PC6-Pad96)") (class "Default")
      (node (ref "U10") (pin "96") (pinfunction "USART6_TX/SDIO_D6/TIM8_CH1/I2S2_MCK/PC6_96") (pintype "bidirectional"))
    )
    (net (code "128") (name "unconnected-(U10-USART6_TX{slash}SPI6_MOSI{slash}FSMC_A25{slash}PG14-Pad129)") (class "Default")
      (node (ref "U10") (pin "129") (pinfunction "USART6_TX/SPI6_MOSI/FSMC_A25/PG14_129") (pintype "bidirectional"))
    )
  )
)
